# Frist_Mechanical_Arm_SCH.net
KiCad netlist of a schematic drawn in Altium Designer
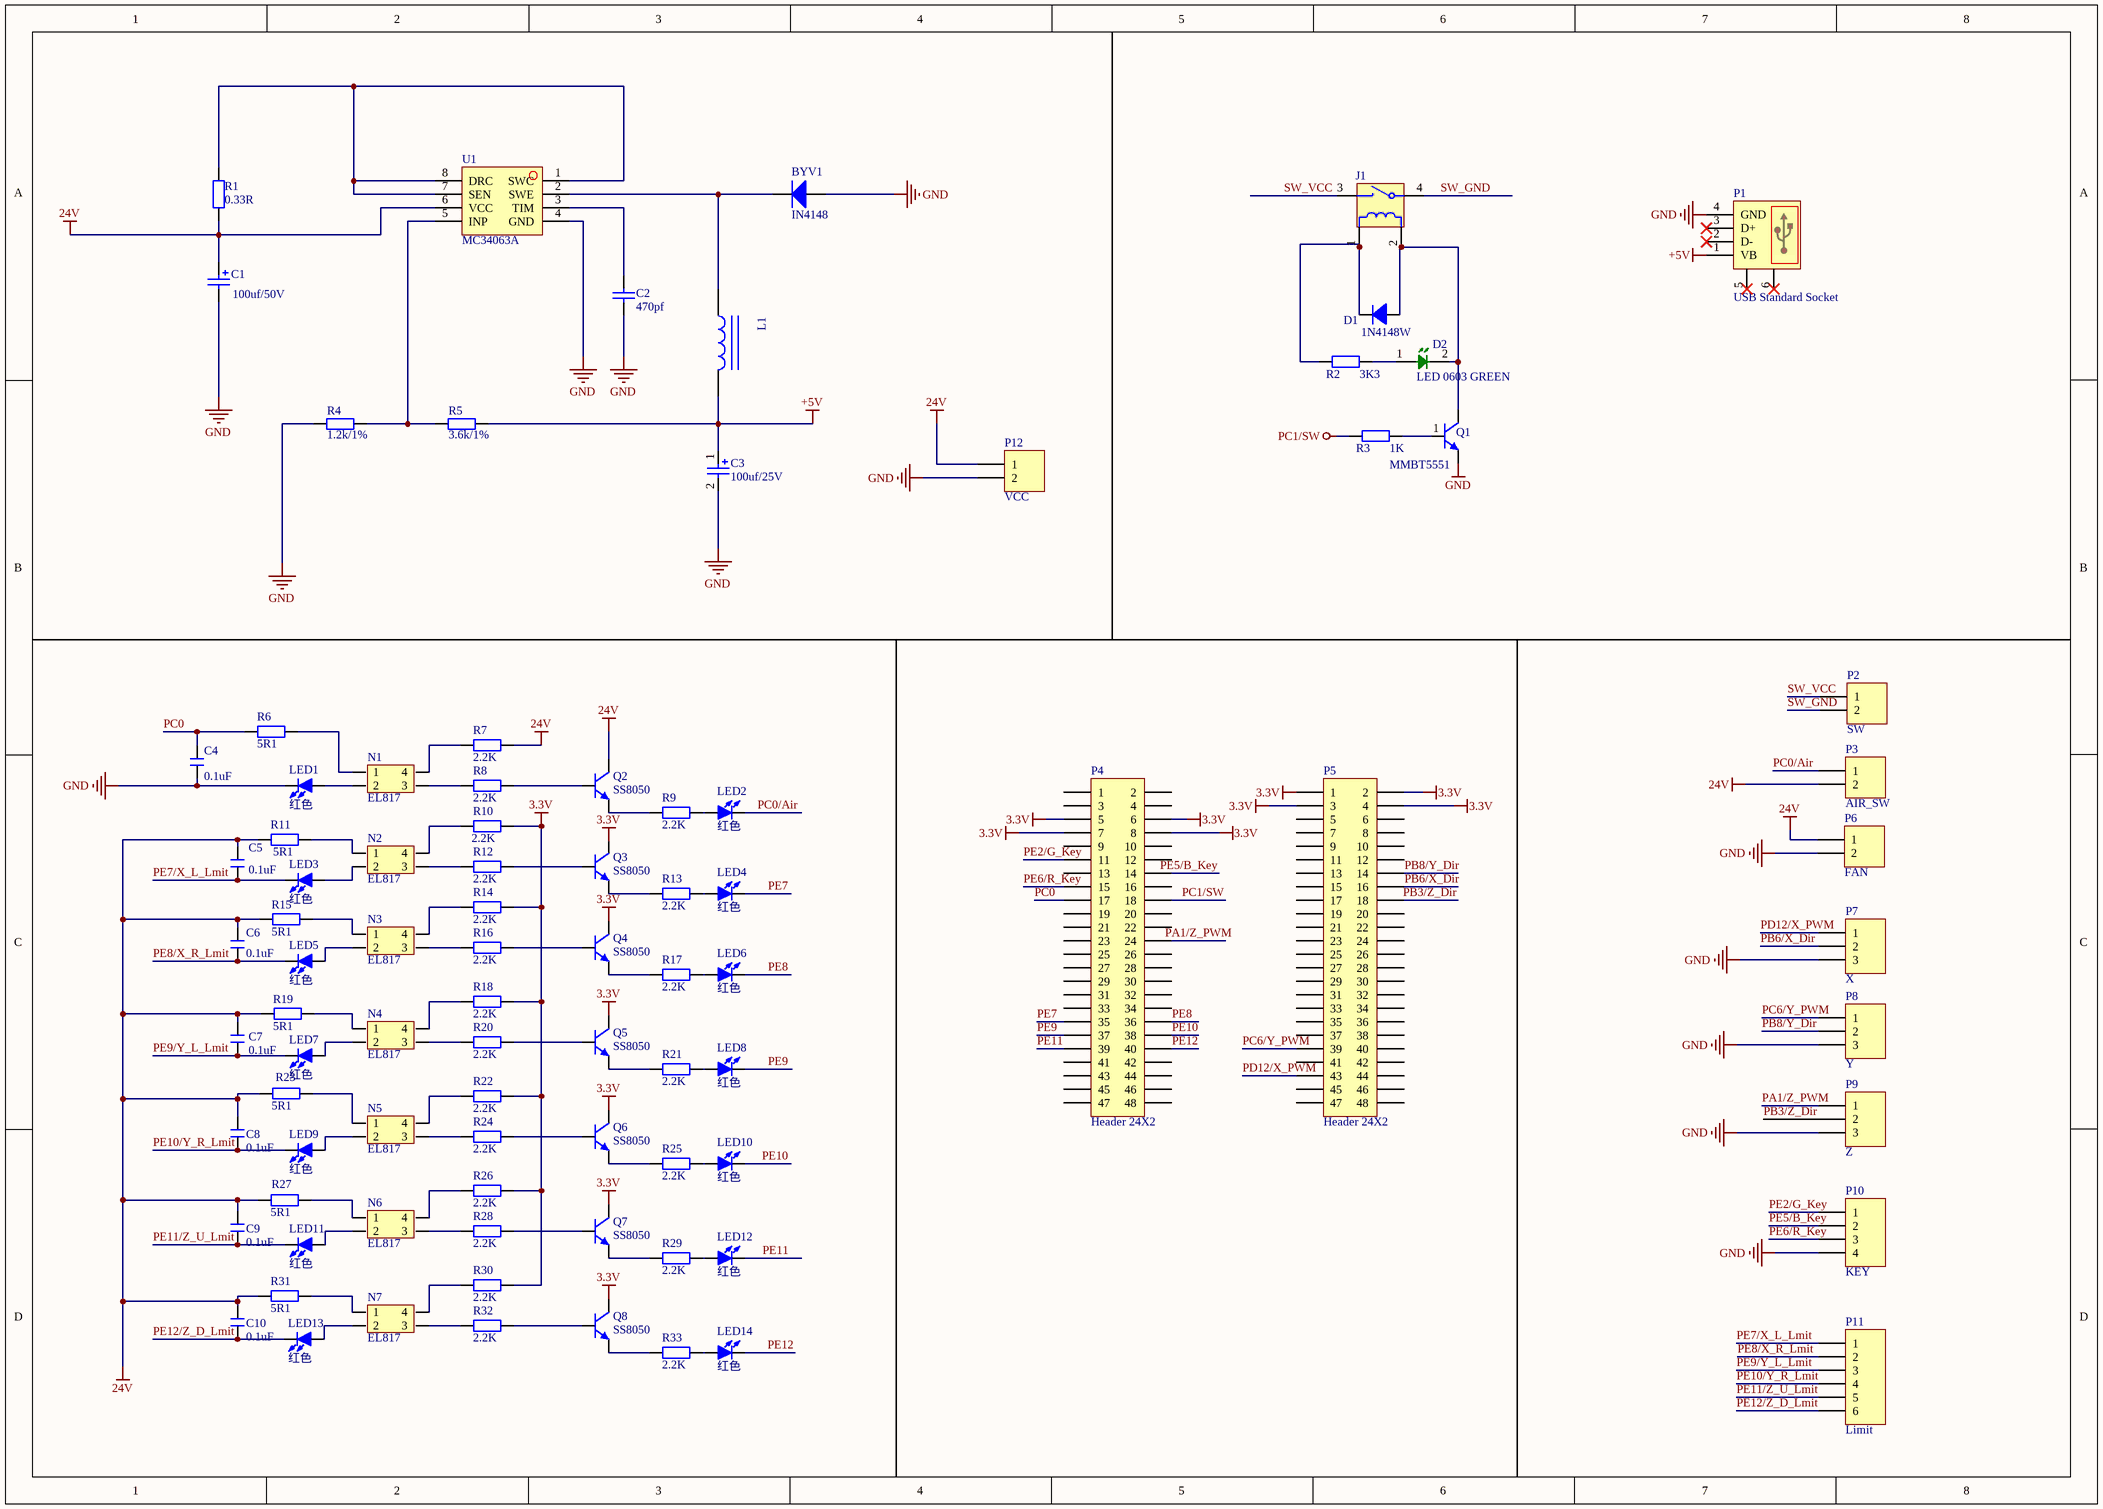
[diagram p0: Frist_Mechanical_Arm_SCH.SchDoc]

(export (version "E")
  (design (tool "Eeschema 10.0.6"))
  (components
    (comp (ref "BYV1")
      (value "BYV10-40")
      (footprint "SMA")
      (description "High Conductance Fast Diode")
      (fields (field (name "MODEL") "IN4148") (field (name "PUBLISHER") "Altium Limited"))
      (libsource (lib "全部3D") (part "Diode  Glass"))
    )
    (comp (ref "C1")
      (value "100uf")
      (footprint "CS 5.0*10*13 - R")
      (description "Polarized Capacitor (Radial)")
      (fields (field (name "VOLTAGE") "100uf/50V") (field (name "PUBLISHER") "Altium Limited"))
      (libsource (lib "全部3D") (part "Cap Pol"))
    )
    (comp (ref "C2")
      (value "470pf")
      (footprint "0603S")
      (description "Capacitor")
      (fields (field (name "PUBLISHER") "Altium Limited"))
      (libsource (lib "充放电") (part "Cap"))
    )
    (comp (ref "C3")
      (value "100uf/25V")
      (footprint "CASE7343")
      (description "Polarized Capacitor (Radial)")
      (fields
        (field (name "VOLTAGE") "16V")
        (field (name "Comment") "Cap Pol")
        (field (name "PUBLISHER") "Altium Limited")
      )
      (libsource (lib "") (part "Cap Pol_1"))
    )
    (comp (ref "C4")
      (value "0.1uF")
      (footprint "C 0805")
      (description "无极性贴片电容")
      (fields (field (name "版权归属") "源创客"))
      (libsource (lib "电阻-电容-电感") (part "C"))
    )
    (comp (ref "C5")
      (value "0.1uF")
      (footprint "C 0805")
      (description "无极性贴片电容")
      (fields (field (name "版权归属") "源创客"))
      (libsource (lib "电阻-电容-电感") (part "C"))
    )
    (comp (ref "C6")
      (value "0.1uF")
      (footprint "C 0805")
      (description "无极性贴片电容")
      (fields (field (name "版权归属") "源创客"))
      (libsource (lib "电阻-电容-电感") (part "C"))
    )
    (comp (ref "C7")
      (value "0.1uF")
      (footprint "C 0805")
      (description "无极性贴片电容")
      (fields (field (name "版权归属") "源创客"))
      (libsource (lib "电阻-电容-电感") (part "C"))
    )
    (comp (ref "C8")
      (value "0.1uF")
      (footprint "C 0805")
      (description "无极性贴片电容")
      (fields (field (name "版权归属") "源创客"))
      (libsource (lib "电阻-电容-电感") (part "C"))
    )
    (comp (ref "C9")
      (value "0.1uF")
      (footprint "C 0805")
      (description "无极性贴片电容")
      (fields (field (name "版权归属") "源创客"))
      (libsource (lib "电阻-电容-电感") (part "C"))
    )
    (comp (ref "C10")
      (value "0.1uF")
      (footprint "C 0805")
      (description "无极性贴片电容")
      (fields (field (name "版权归属") "源创客"))
      (libsource (lib "电阻-电容-电感") (part "C"))
    )
    (comp (ref "D1")
      (value "1N4148W")
      (footprint "SOD123")
      (description "HIGH-SPEED   SWITCHING DIODE")
      (libsource (lib "My Component") (part "Diode"))
    )
    (comp (ref "D2")
      (value "LED 0603 GREEN")
      (footprint "LED0805")
      (libsource (lib "My Component") (part "LED 0603 GREEN"))
    )
    (comp (ref "J1") (value "JDQ") (footprint "APAN3112") (libsource (lib "My Component") (part "PA1a")))
    (comp (ref "L1")
      (value "~")
      (footprint "L-SMD1010")
      (description "Magnetic-Core Inductor")
      (fields (field (name "PUBLISHER") "Altium Limited"))
      (libsource (lib "全部3D") (part "Inductor Iron"))
    )
    (comp (ref "LED1")
      (value "红色")
      (footprint "LED 0805G")
      (description "贴片LED")
      (fields (field (name "版权归属") "源创客"))
      (libsource (lib "LED") (part "LED-SMD"))
    )
    (comp (ref "LED2")
      (value "红色")
      (footprint "LED 0805G")
      (description "贴片LED")
      (fields (field (name "版权归属") "源创客"))
      (libsource (lib "LED") (part "LED-SMD"))
    )
    (comp (ref "LED3")
      (value "红色")
      (footprint "LED 0805G")
      (description "贴片LED")
      (fields (field (name "版权归属") "源创客"))
      (libsource (lib "LED") (part "LED-SMD"))
    )
    (comp (ref "LED4")
      (value "红色")
      (footprint "LED 0805G")
      (description "贴片LED")
      (fields (field (name "版权归属") "源创客"))
      (libsource (lib "LED") (part "LED-SMD"))
    )
    (comp (ref "LED5")
      (value "红色")
      (footprint "LED 0805G")
      (description "贴片LED")
      (fields (field (name "版权归属") "源创客"))
      (libsource (lib "LED") (part "LED-SMD"))
    )
    (comp (ref "LED6")
      (value "红色")
      (footprint "LED 0805G")
      (description "贴片LED")
      (fields (field (name "版权归属") "源创客"))
      (libsource (lib "LED") (part "LED-SMD"))
    )
    (comp (ref "LED7")
      (value "红色")
      (footprint "LED 0805G")
      (description "贴片LED")
      (fields (field (name "版权归属") "源创客"))
      (libsource (lib "LED") (part "LED-SMD"))
    )
    (comp (ref "LED8")
      (value "红色")
      (footprint "LED 0805G")
      (description "贴片LED")
      (fields (field (name "版权归属") "源创客"))
      (libsource (lib "LED") (part "LED-SMD"))
    )
    (comp (ref "LED9")
      (value "红色")
      (footprint "LED 0805G")
      (description "贴片LED")
      (fields (field (name "版权归属") "源创客"))
      (libsource (lib "LED") (part "LED-SMD"))
    )
    (comp (ref "LED10")
      (value "红色")
      (footprint "LED 0805G")
      (description "贴片LED")
      (fields (field (name "版权归属") "源创客"))
      (libsource (lib "LED") (part "LED-SMD"))
    )
    (comp (ref "LED11")
      (value "红色")
      (footprint "LED 0805G")
      (description "贴片LED")
      (fields (field (name "版权归属") "源创客"))
      (libsource (lib "LED") (part "LED-SMD"))
    )
    (comp (ref "LED12")
      (value "红色")
      (footprint "LED 0805G")
      (description "贴片LED")
      (fields (field (name "版权归属") "源创客"))
      (libsource (lib "LED") (part "LED-SMD"))
    )
    (comp (ref "LED13")
      (value "红色")
      (footprint "LED 0805G")
      (description "贴片LED")
      (fields (field (name "版权归属") "源创客"))
      (libsource (lib "LED") (part "LED-SMD"))
    )
    (comp (ref "LED14")
      (value "红色")
      (footprint "LED 0805G")
      (description "贴片LED")
      (fields (field (name "版权归属") "源创客"))
      (libsource (lib "LED") (part "LED-SMD"))
    )
    (comp (ref "N1") (value "EL817") (footprint "LC-DIP-4") (libsource (lib "我的器件") (part "EL817")))
    (comp (ref "N2") (value "EL817") (footprint "LC-DIP-4") (libsource (lib "我的器件") (part "EL817")))
    (comp (ref "N3") (value "EL817") (footprint "LC-DIP-4") (libsource (lib "我的器件") (part "EL817")))
    (comp (ref "N4") (value "EL817") (footprint "LC-DIP-4") (libsource (lib "我的器件") (part "EL817")))
    (comp (ref "N5") (value "EL817") (footprint "LC-DIP-4") (libsource (lib "我的器件") (part "EL817")))
    (comp (ref "N6") (value "EL817") (footprint "LC-DIP-4") (libsource (lib "我的器件") (part "EL817")))
    (comp (ref "N7") (value "EL817") (footprint "LC-DIP-4") (libsource (lib "我的器件") (part "EL817")))
    (comp (ref "P1")
      (value "USB Standard Socket")
      (footprint "USB Standard Socket")
      (libsource (lib "My Component") (part "USB Standard Socket"))
    )
    (comp (ref "P2")
      (value "SW")
      (footprint "KF128-3.81-2P")
      (description "Header, 2-Pin")
      (fields (field (name "PUBLISHER") "Altium Limited"))
      (libsource (lib "Miscellaneous Connectors") (part "Header 2"))
    )
    (comp (ref "P3")
      (value "AIR_SW")
      (footprint "KF128-5.08-2P")
      (description "Header, 2-Pin")
      (fields (field (name "PUBLISHER") "Altium Limited"))
      (libsource (lib "Miscellaneous Connectors") (part "Header 2"))
    )
    (comp (ref "P4")
      (value "Header 24X2")
      (footprint "HDR2X24")
      (description "Header, 24-Pin, Dual row")
      (fields (field (name "PUBLISHER") "Altium Limited"))
      (libsource (lib "Miscellaneous Connectors") (part "Header 24X2"))
    )
    (comp (ref "P5")
      (value "Header 24X2")
      (footprint "HDR2X24")
      (description "Header, 24-Pin, Dual row")
      (fields (field (name "PUBLISHER") "Altium Limited"))
      (libsource (lib "Miscellaneous Connectors") (part "Header 24X2"))
    )
    (comp (ref "P6")
      (value "FAN")
      (footprint "KF128-5.08-2P")
      (description "Header, 2-Pin")
      (fields (field (name "PUBLISHER") "Altium Limited"))
      (libsource (lib "Miscellaneous Connectors") (part "Header 2"))
    )
    (comp (ref "P7")
      (value "X")
      (footprint "KF128-5.08-3P")
      (description "Header, 3-Pin")
      (fields (field (name "PUBLISHER") "Altium Limited"))
      (libsource (lib "Miscellaneous Connectors") (part "Header 3"))
    )
    (comp (ref "P8")
      (value "Y")
      (footprint "KF128-5.08-3P")
      (description "Header, 3-Pin")
      (fields (field (name "PUBLISHER") "Altium Limited"))
      (libsource (lib "Miscellaneous Connectors") (part "Header 3"))
    )
    (comp (ref "P9")
      (value "Z")
      (footprint "KF128-5.08-3P")
      (description "Header, 3-Pin")
      (fields (field (name "PUBLISHER") "Altium Limited"))
      (libsource (lib "Miscellaneous Connectors") (part "Header 3"))
    )
    (comp (ref "P10")
      (value "KEY")
      (footprint "KF128-5.08-4P")
      (description "Header, 4-Pin")
      (fields (field (name "PUBLISHER") "Altium Limited"))
      (libsource (lib "Miscellaneous Connectors") (part "Header 4"))
    )
    (comp (ref "P11")
      (value "Limit")
      (footprint "KF128-5.08-6P")
      (description "Header, 6-Pin")
      (fields (field (name "PUBLISHER") "Altium Limited"))
      (libsource (lib "Miscellaneous Connectors") (part "Header 6"))
    )
    (comp (ref "P12")
      (value "VCC")
      (footprint "KF128-5.08-2P")
      (description "Header, 2-Pin")
      (fields (field (name "PUBLISHER") "Altium Limited"))
      (libsource (lib "Miscellaneous Connectors") (part "Header 2"))
    )
    (comp (ref "Q1")
      (value "MMBT5551")
      (footprint "SOT23-3")
      (description "SOT-23 Plastic-Encapsulate Transistors")
      (libsource (lib "My Component") (part "NPN"))
    )
    (comp (ref "Q2")
      (value "SS8050")
      (footprint "SOT23-3N")
      (description "高频放大-NPN型")
      (fields (field (name "版权归属") "源创客"))
      (libsource (lib "三极管") (part "8050-SMD"))
    )
    (comp (ref "Q3")
      (value "SS8050")
      (footprint "SOT23-3N")
      (description "高频放大-NPN型")
      (fields (field (name "版权归属") "源创客"))
      (libsource (lib "三极管") (part "8050-SMD"))
    )
    (comp (ref "Q4")
      (value "SS8050")
      (footprint "SOT23-3N")
      (description "高频放大-NPN型")
      (fields (field (name "版权归属") "源创客"))
      (libsource (lib "三极管") (part "8050-SMD"))
    )
    (comp (ref "Q5")
      (value "SS8050")
      (footprint "SOT23-3N")
      (description "高频放大-NPN型")
      (fields (field (name "版权归属") "源创客"))
      (libsource (lib "三极管") (part "8050-SMD"))
    )
    (comp (ref "Q6")
      (value "SS8050")
      (footprint "SOT23-3N")
      (description "高频放大-NPN型")
      (fields (field (name "版权归属") "源创客"))
      (libsource (lib "三极管") (part "8050-SMD"))
    )
    (comp (ref "Q7")
      (value "SS8050")
      (footprint "SOT23-3N")
      (description "高频放大-NPN型")
      (fields (field (name "版权归属") "源创客"))
      (libsource (lib "三极管") (part "8050-SMD"))
    )
    (comp (ref "Q8")
      (value "SS8050")
      (footprint "SOT23-3N")
      (description "高频放大-NPN型")
      (fields (field (name "版权归属") "源创客"))
      (libsource (lib "三极管") (part "8050-SMD"))
    )
    (comp (ref "R1")
      (value "0.33R")
      (footprint "1206R")
      (description "Resistor")
      (fields (field (name "TOLERANCE") "1%"))
      (libsource (lib "充放电") (part "Res2"))
    )
    (comp (ref "R2")
      (value "3K3")
      (footprint "0603R")
      (description "Resistor")
      (fields (field (name "TOLERANCE") "5%"))
      (libsource (lib "Miscellaneous Devices") (part "Res2"))
    )
    (comp (ref "R3")
      (value "1K")
      (footprint "0603R")
      (description "Resistor")
      (fields (field (name "TOLERANCE") "5%"))
      (libsource (lib "Miscellaneous Devices") (part "Res2"))
    )
    (comp (ref "R4")
      (value "1.2k/1%")
      (footprint "0603R")
      (description "Resistor")
      (fields (field (name "TOLERANCE") "1%"))
      (libsource (lib "") (part "Res2_1"))
    )
    (comp (ref "R5")
      (value "3.6k/1%")
      (footprint "0603R")
      (description "Resistor")
      (fields (field (name "TOLERANCE") "1%"))
      (libsource (lib "") (part "Res2_1"))
    )
    (comp (ref "R6")
      (value "5R1")
      (footprint "R 0805")
      (description "贴片电阻")
      (fields (field (name "版权归属") "源创客"))
      (libsource (lib "电阻-电容-电感") (part "R"))
    )
    (comp (ref "R7")
      (value "2.2K")
      (footprint "R 0805")
      (description "贴片电阻")
      (fields (field (name "版权归属") "源创客"))
      (libsource (lib "电阻-电容-电感") (part "R"))
    )
    (comp (ref "R8")
      (value "2.2K")
      (footprint "R 0805")
      (description "贴片电阻")
      (fields (field (name "版权归属") "源创客"))
      (libsource (lib "电阻-电容-电感") (part "R"))
    )
    (comp (ref "R9")
      (value "2.2K")
      (footprint "R 0805")
      (description "贴片电阻")
      (fields (field (name "版权归属") "源创客"))
      (libsource (lib "电阻-电容-电感") (part "R"))
    )
    (comp (ref "R10")
      (value "2.2K")
      (footprint "R 0805")
      (description "贴片电阻")
      (fields (field (name "版权归属") "源创客"))
      (libsource (lib "电阻-电容-电感") (part "R"))
    )
    (comp (ref "R11")
      (value "5R1")
      (footprint "R 0805")
      (description "贴片电阻")
      (fields (field (name "版权归属") "源创客"))
      (libsource (lib "电阻-电容-电感") (part "R"))
    )
    (comp (ref "R12")
      (value "2.2K")
      (footprint "R 0805")
      (description "贴片电阻")
      (fields (field (name "版权归属") "源创客"))
      (libsource (lib "电阻-电容-电感") (part "R"))
    )
    (comp (ref "R13")
      (value "2.2K")
      (footprint "R 0805")
      (description "贴片电阻")
      (fields (field (name "版权归属") "源创客"))
      (libsource (lib "电阻-电容-电感") (part "R"))
    )
    (comp (ref "R14")
      (value "2.2K")
      (footprint "R 0805")
      (description "贴片电阻")
      (fields (field (name "版权归属") "源创客"))
      (libsource (lib "电阻-电容-电感") (part "R"))
    )
    (comp (ref "R15")
      (value "5R1")
      (footprint "R 0805")
      (description "贴片电阻")
      (fields (field (name "版权归属") "源创客"))
      (libsource (lib "电阻-电容-电感") (part "R"))
    )
    (comp (ref "R16")
      (value "2.2K")
      (footprint "R 0805")
      (description "贴片电阻")
      (fields (field (name "版权归属") "源创客"))
      (libsource (lib "电阻-电容-电感") (part "R"))
    )
    (comp (ref "R17")
      (value "2.2K")
      (footprint "R 0805")
      (description "贴片电阻")
      (fields (field (name "版权归属") "源创客"))
      (libsource (lib "电阻-电容-电感") (part "R"))
    )
    (comp (ref "R18")
      (value "2.2K")
      (footprint "R 0805")
      (description "贴片电阻")
      (fields (field (name "版权归属") "源创客"))
      (libsource (lib "电阻-电容-电感") (part "R"))
    )
    (comp (ref "R19")
      (value "5R1")
      (footprint "R 0805")
      (description "贴片电阻")
      (fields (field (name "版权归属") "源创客"))
      (libsource (lib "电阻-电容-电感") (part "R"))
    )
    (comp (ref "R20")
      (value "2.2K")
      (footprint "R 0805")
      (description "贴片电阻")
      (fields (field (name "版权归属") "源创客"))
      (libsource (lib "电阻-电容-电感") (part "R"))
    )
    (comp (ref "R21")
      (value "2.2K")
      (footprint "R 0805")
      (description "贴片电阻")
      (fields (field (name "版权归属") "源创客"))
      (libsource (lib "电阻-电容-电感") (part "R"))
    )
    (comp (ref "R22")
      (value "2.2K")
      (footprint "R 0805")
      (description "贴片电阻")
      (fields (field (name "版权归属") "源创客"))
      (libsource (lib "电阻-电容-电感") (part "R"))
    )
    (comp (ref "R23")
      (value "5R1")
      (footprint "R 0805")
      (description "贴片电阻")
      (fields (field (name "版权归属") "源创客"))
      (libsource (lib "电阻-电容-电感") (part "R"))
    )
    (comp (ref "R24")
      (value "2.2K")
      (footprint "R 0805")
      (description "贴片电阻")
      (fields (field (name "版权归属") "源创客"))
      (libsource (lib "电阻-电容-电感") (part "R"))
    )
    (comp (ref "R25")
      (value "2.2K")
      (footprint "R 0805")
      (description "贴片电阻")
      (fields (field (name "版权归属") "源创客"))
      (libsource (lib "电阻-电容-电感") (part "R"))
    )
    (comp (ref "R26")
      (value "2.2K")
      (footprint "R 0805")
      (description "贴片电阻")
      (fields (field (name "版权归属") "源创客"))
      (libsource (lib "电阻-电容-电感") (part "R"))
    )
    (comp (ref "R27")
      (value "5R1")
      (footprint "R 0805")
      (description "贴片电阻")
      (fields (field (name "版权归属") "源创客"))
      (libsource (lib "电阻-电容-电感") (part "R"))
    )
    (comp (ref "R28")
      (value "2.2K")
      (footprint "R 0805")
      (description "贴片电阻")
      (fields (field (name "版权归属") "源创客"))
      (libsource (lib "电阻-电容-电感") (part "R"))
    )
    (comp (ref "R29")
      (value "2.2K")
      (footprint "R 0805")
      (description "贴片电阻")
      (fields (field (name "版权归属") "源创客"))
      (libsource (lib "电阻-电容-电感") (part "R"))
    )
    (comp (ref "R30")
      (value "2.2K")
      (footprint "R 0805")
      (description "贴片电阻")
      (fields (field (name "版权归属") "源创客"))
      (libsource (lib "电阻-电容-电感") (part "R"))
    )
    (comp (ref "R31")
      (value "5R1")
      (footprint "R 0805")
      (description "贴片电阻")
      (fields (field (name "版权归属") "源创客"))
      (libsource (lib "电阻-电容-电感") (part "R"))
    )
    (comp (ref "R32")
      (value "2.2K")
      (footprint "R 0805")
      (description "贴片电阻")
      (fields (field (name "版权归属") "源创客"))
      (libsource (lib "电阻-电容-电感") (part "R"))
    )
    (comp (ref "R33")
      (value "2.2K")
      (footprint "R 0805")
      (description "贴片电阻")
      (fields (field (name "版权归属") "源创客"))
      (libsource (lib "电阻-电容-电感") (part "R"))
    )
    (comp (ref "U1") (value "MC34063A") (footprint "SOP-8") (libsource (lib "SWLiB") (part "MC34063A")))
  )
  (nets
    (net (code "1") (name "+5V") (class "Default")
      (node (ref "C3") (pin "1") (pinfunction "1_1") (pintype "passive"))
      (node (ref "L1") (pin "2") (pinfunction "2_2") (pintype "passive"))
      (node (ref "P1") (pin "1") (pinfunction "VB_1") (pintype "passive"))
      (node (ref "R5") (pin "2") (pinfunction "2_2") (pintype "passive"))
    )
    (net (code "2") (name "/PA1{slash}Z_PWM") (class "Default")
      (node (ref "P4") (pin "24") (pinfunction "24_24") (pintype "passive"))
      (node (ref "P9") (pin "1") (pinfunction "1_1") (pintype "passive"))
    )
    (net (code "3") (name "/PB3{slash}Z_Dir") (class "Default")
      (node (ref "P5") (pin "18") (pinfunction "18_18") (pintype "passive"))
      (node (ref "P9") (pin "2") (pinfunction "2_2") (pintype "passive"))
    )
    (net (code "4") (name "/PB6{slash}X_Dir") (class "Default")
      (node (ref "P5") (pin "16") (pinfunction "16_16") (pintype "passive"))
      (node (ref "P7") (pin "2") (pinfunction "2_2") (pintype "passive"))
    )
    (net (code "5") (name "/PB8{slash}Y_Dir") (class "Default")
      (node (ref "P5") (pin "14") (pinfunction "14_14") (pintype "passive"))
      (node (ref "P8") (pin "2") (pinfunction "2_2") (pintype "passive"))
    )
    (net (code "6") (name "/PC0") (class "Default")
      (node (ref "C4") (pin "1") (pinfunction "1_1") (pintype "passive"))
      (node (ref "P4") (pin "17") (pinfunction "17_17") (pintype "passive"))
      (node (ref "R6") (pin "1") (pinfunction "1_1") (pintype "passive"))
    )
    (net (code "7") (name "/PC0{slash}Air") (class "Default")
      (node (ref "LED2") (pin "2") (pinfunction "K_2") (pintype "passive"))
      (node (ref "P3") (pin "1") (pinfunction "1_1") (pintype "passive"))
    )
    (net (code "8") (name "/PC6{slash}Y_PWM") (class "Default")
      (node (ref "P5") (pin "39") (pinfunction "39_39") (pintype "passive"))
      (node (ref "P8") (pin "1") (pinfunction "1_1") (pintype "passive"))
    )
    (net (code "9") (name "/PD12{slash}X_PWM") (class "Default")
      (node (ref "P5") (pin "43") (pinfunction "43_43") (pintype "passive"))
      (node (ref "P7") (pin "1") (pinfunction "1_1") (pintype "passive"))
    )
    (net (code "10") (name "/PE2{slash}G_Key") (class "Default")
      (node (ref "P10") (pin "1") (pinfunction "1_1") (pintype "passive"))
      (node (ref "P4") (pin "11") (pinfunction "11_11") (pintype "passive"))
    )
    (net (code "11") (name "/PE5{slash}B_Key") (class "Default")
      (node (ref "P10") (pin "2") (pinfunction "2_2") (pintype "passive"))
      (node (ref "P4") (pin "14") (pinfunction "14_14") (pintype "passive"))
    )
    (net (code "12") (name "/PE6{slash}R_Key") (class "Default")
      (node (ref "P10") (pin "3") (pinfunction "3_3") (pintype "passive"))
      (node (ref "P4") (pin "15") (pinfunction "15_15") (pintype "passive"))
    )
    (net (code "13") (name "/PE7") (class "Default")
      (node (ref "LED4") (pin "2") (pinfunction "K_2") (pintype "passive"))
      (node (ref "P4") (pin "35") (pinfunction "35_35") (pintype "passive"))
    )
    (net (code "14") (name "/PE7{slash}X_L_Lmit") (class "Default")
      (node (ref "C5") (pin "1") (pinfunction "1_1") (pintype "passive"))
      (node (ref "LED3") (pin "2") (pinfunction "K_2") (pintype "passive"))
      (node (ref "P11") (pin "1") (pinfunction "1_1") (pintype "passive"))
    )
    (net (code "15") (name "/PE8") (class "Default")
      (node (ref "LED6") (pin "2") (pinfunction "K_2") (pintype "passive"))
      (node (ref "P4") (pin "36") (pinfunction "36_36") (pintype "passive"))
    )
    (net (code "16") (name "/PE8{slash}X_R_Lmit") (class "Default")
      (node (ref "C6") (pin "1") (pinfunction "1_1") (pintype "passive"))
      (node (ref "LED5") (pin "2") (pinfunction "K_2") (pintype "passive"))
      (node (ref "P11") (pin "2") (pinfunction "2_2") (pintype "passive"))
    )
    (net (code "17") (name "/PE9") (class "Default")
      (node (ref "LED8") (pin "2") (pinfunction "K_2") (pintype "passive"))
      (node (ref "P4") (pin "37") (pinfunction "37_37") (pintype "passive"))
    )
    (net (code "18") (name "/PE9{slash}Y_L_Lmit") (class "Default")
      (node (ref "C7") (pin "1") (pinfunction "1_1") (pintype "passive"))
      (node (ref "LED7") (pin "2") (pinfunction "K_2") (pintype "passive"))
      (node (ref "P11") (pin "3") (pinfunction "3_3") (pintype "passive"))
    )
    (net (code "19") (name "/PE10") (class "Default")
      (node (ref "LED10") (pin "2") (pinfunction "K_2") (pintype "passive"))
      (node (ref "P4") (pin "38") (pinfunction "38_38") (pintype "passive"))
    )
    (net (code "20") (name "/PE10{slash}Y_R_Lmit") (class "Default")
      (node (ref "C8") (pin "1") (pinfunction "1_1") (pintype "passive"))
      (node (ref "LED9") (pin "2") (pinfunction "K_2") (pintype "passive"))
      (node (ref "P11") (pin "4") (pinfunction "4_4") (pintype "passive"))
    )
    (net (code "21") (name "/PE11") (class "Default")
      (node (ref "LED12") (pin "2") (pinfunction "K_2") (pintype "passive"))
      (node (ref "P4") (pin "39") (pinfunction "39_39") (pintype "passive"))
    )
    (net (code "22") (name "/PE11{slash}Z_U_Lmit") (class "Default")
      (node (ref "C9") (pin "1") (pinfunction "1_1") (pintype "passive"))
      (node (ref "LED11") (pin "2") (pinfunction "K_2") (pintype "passive"))
      (node (ref "P11") (pin "5") (pinfunction "5_5") (pintype "passive"))
    )
    (net (code "23") (name "/PE12") (class "Default")
      (node (ref "LED14") (pin "2") (pinfunction "K_2") (pintype "passive"))
      (node (ref "P4") (pin "40") (pinfunction "40_40") (pintype "passive"))
    )
    (net (code "24") (name "/PE12{slash}Z_D_Lmit") (class "Default")
      (node (ref "C10") (pin "1") (pinfunction "1_1") (pintype "passive"))
      (node (ref "LED13") (pin "2") (pinfunction "K_2") (pintype "passive"))
      (node (ref "P11") (pin "6") (pinfunction "6_6") (pintype "passive"))
    )
    (net (code "25") (name "/SW_GND") (class "Default")
      (node (ref "J1") (pin "4") (pinfunction "4_4") (pintype "passive"))
      (node (ref "P2") (pin "2") (pinfunction "2_2") (pintype "passive"))
    )
    (net (code "26") (name "/SW_VCC") (class "Default")
      (node (ref "J1") (pin "3") (pinfunction "3_3") (pintype "passive"))
      (node (ref "P2") (pin "1") (pinfunction "1_1") (pintype "passive"))
    )
    (net (code "27") (name "3.3V") (class "Default")
      (node (ref "P4") (pin "5") (pinfunction "5_5") (pintype "passive"))
      (node (ref "P4") (pin "6") (pinfunction "6_6") (pintype "passive"))
      (node (ref "P4") (pin "7") (pinfunction "7_7") (pintype "passive"))
      (node (ref "P4") (pin "8") (pinfunction "8_8") (pintype "passive"))
      (node (ref "P5") (pin "1") (pinfunction "1_1") (pintype "passive"))
      (node (ref "P5") (pin "2") (pinfunction "2_2") (pintype "passive"))
      (node (ref "P5") (pin "3") (pinfunction "3_3") (pintype "passive"))
      (node (ref "P5") (pin "4") (pinfunction "4_4") (pintype "passive"))
      (node (ref "Q4") (pin "3") (pinfunction "C_3") (pintype "passive"))
      (node (ref "Q5") (pin "3") (pinfunction "C_3") (pintype "passive"))
      (node (ref "Q6") (pin "3") (pinfunction "C_3") (pintype "passive"))
      (node (ref "Q7") (pin "3") (pinfunction "C_3") (pintype "passive"))
      (node (ref "Q8") (pin "3") (pinfunction "C_3") (pintype "passive"))
      (node (ref "R10") (pin "2") (pinfunction "2_2") (pintype "passive"))
      (node (ref "R14") (pin "2") (pinfunction "2_2") (pintype "passive"))
      (node (ref "R18") (pin "2") (pinfunction "2_2") (pintype "passive"))
      (node (ref "R22") (pin "2") (pinfunction "2_2") (pintype "passive"))
      (node (ref "R26") (pin "2") (pinfunction "2_2") (pintype "passive"))
      (node (ref "R30") (pin "2") (pinfunction "2_2") (pintype "passive"))
    )
    (net (code "28") (name "24V") (class "Default")
      (node (ref "C1") (pin "1") (pinfunction "1_1") (pintype "passive"))
      (node (ref "C10") (pin "2") (pinfunction "2_2") (pintype "passive"))
      (node (ref "C5") (pin "2") (pinfunction "2_2") (pintype "passive"))
      (node (ref "C6") (pin "2") (pinfunction "2_2") (pintype "passive"))
      (node (ref "C7") (pin "2") (pinfunction "2_2") (pintype "passive"))
      (node (ref "C8") (pin "2") (pinfunction "2_2") (pintype "passive"))
      (node (ref "C9") (pin "2") (pinfunction "2_2") (pintype "passive"))
      (node (ref "P12") (pin "1") (pinfunction "1_1") (pintype "passive"))
      (node (ref "P3") (pin "2") (pinfunction "2_2") (pintype "passive"))
      (node (ref "P6") (pin "1") (pinfunction "1_1") (pintype "passive"))
      (node (ref "Q2") (pin "3") (pinfunction "C_3") (pintype "passive"))
      (node (ref "R1") (pin "1") (pinfunction "1_1") (pintype "passive"))
      (node (ref "R11") (pin "1") (pinfunction "1_1") (pintype "passive"))
      (node (ref "R15") (pin "1") (pinfunction "1_1") (pintype "passive"))
      (node (ref "R19") (pin "1") (pinfunction "1_1") (pintype "passive"))
      (node (ref "R23") (pin "1") (pinfunction "1_1") (pintype "passive"))
      (node (ref "R27") (pin "1") (pinfunction "1_1") (pintype "passive"))
      (node (ref "R31") (pin "1") (pinfunction "1_1") (pintype "passive"))
      (node (ref "R7") (pin "2") (pinfunction "2_2") (pintype "passive"))
      (node (ref "U1") (pin "6") (pinfunction "VCC_6") (pintype "passive"))
    )
    (net (code "29") (name "GND") (class "Default")
      (node (ref "BYV1") (pin "1") (pinfunction "A_1") (pintype "passive"))
      (node (ref "C1") (pin "2") (pinfunction "2_2") (pintype "passive"))
      (node (ref "C2") (pin "1") (pinfunction "1_1") (pintype "passive"))
      (node (ref "C3") (pin "2") (pinfunction "2_2") (pintype "passive"))
      (node (ref "C4") (pin "2") (pinfunction "2_2") (pintype "passive"))
      (node (ref "LED1") (pin "2") (pinfunction "K_2") (pintype "passive"))
      (node (ref "P1") (pin "4") (pinfunction "GND_4") (pintype "passive"))
      (node (ref "P10") (pin "4") (pinfunction "4_4") (pintype "passive"))
      (node (ref "P12") (pin "2") (pinfunction "2_2") (pintype "passive"))
      (node (ref "P6") (pin "2") (pinfunction "2_2") (pintype "passive"))
      (node (ref "P7") (pin "3") (pinfunction "3_3") (pintype "passive"))
      (node (ref "P8") (pin "3") (pinfunction "3_3") (pintype "passive"))
      (node (ref "P9") (pin "3") (pinfunction "3_3") (pintype "passive"))
      (node (ref "Q1") (pin "2") (pintype "passive"))
      (node (ref "R4") (pin "1") (pinfunction "1_1") (pintype "passive"))
      (node (ref "U1") (pin "4") (pinfunction "GND_4") (pintype "passive"))
    )
    (net (code "30") (name "Net-(BYV1-K)") (class "Default")
      (node (ref "BYV1") (pin "2") (pinfunction "K_2") (pintype "passive"))
      (node (ref "L1") (pin "1") (pinfunction "1_1") (pintype "passive"))
      (node (ref "U1") (pin "2") (pinfunction "SWE_2") (pintype "passive"))
    )
    (net (code "31") (name "Net-(D1-A)") (class "Default")
      (node (ref "D1") (pin "1") (pinfunction "A_1") (pintype "passive"))
      (node (ref "D2") (pin "2") (pinfunction "2_2") (pintype "passive"))
      (node (ref "J1") (pin "2") (pinfunction "2_2") (pintype "passive"))
      (node (ref "Q1") (pin "3") (pintype "passive"))
    )
    (net (code "32") (name "Net-(D1-K)") (class "Default")
      (node (ref "D1") (pin "2") (pinfunction "K_2") (pintype "passive"))
      (node (ref "J1") (pin "1") (pinfunction "1_1") (pintype "passive"))
      (node (ref "R2") (pin "1") (pinfunction "1_1") (pintype "passive"))
    )
    (net (code "33") (name "Net-(D2-Pad1)") (class "Default")
      (node (ref "D2") (pin "1") (pinfunction "1_1") (pintype "passive"))
      (node (ref "R2") (pin "2") (pinfunction "2_2") (pintype "passive"))
    )
    (net (code "34") (name "Net-(LED1-A)") (class "Default")
      (node (ref "LED1") (pin "1") (pinfunction "A_1") (pintype "passive"))
      (node (ref "N1") (pin "2") (pinfunction "2_2") (pintype "passive"))
    )
    (net (code "35") (name "Net-(LED2-A)") (class "Default")
      (node (ref "LED2") (pin "1") (pinfunction "A_1") (pintype "passive"))
      (node (ref "R9") (pin "2") (pinfunction "2_2") (pintype "passive"))
    )
    (net (code "36") (name "Net-(LED3-A)") (class "Default")
      (node (ref "LED3") (pin "1") (pinfunction "A_1") (pintype "passive"))
      (node (ref "N2") (pin "2") (pinfunction "2_2") (pintype "passive"))
    )
    (net (code "37") (name "Net-(LED4-A)") (class "Default")
      (node (ref "LED4") (pin "1") (pinfunction "A_1") (pintype "passive"))
      (node (ref "R13") (pin "2") (pinfunction "2_2") (pintype "passive"))
    )
    (net (code "38") (name "Net-(LED5-A)") (class "Default")
      (node (ref "LED5") (pin "1") (pinfunction "A_1") (pintype "passive"))
      (node (ref "N3") (pin "2") (pinfunction "2_2") (pintype "passive"))
    )
    (net (code "39") (name "Net-(LED6-A)") (class "Default")
      (node (ref "LED6") (pin "1") (pinfunction "A_1") (pintype "passive"))
      (node (ref "R17") (pin "2") (pinfunction "2_2") (pintype "passive"))
    )
    (net (code "40") (name "Net-(LED7-A)") (class "Default")
      (node (ref "LED7") (pin "1") (pinfunction "A_1") (pintype "passive"))
      (node (ref "N4") (pin "2") (pinfunction "2_2") (pintype "passive"))
    )
    (net (code "41") (name "Net-(LED8-A)") (class "Default")
      (node (ref "LED8") (pin "1") (pinfunction "A_1") (pintype "passive"))
      (node (ref "R21") (pin "2") (pinfunction "2_2") (pintype "passive"))
    )
    (net (code "42") (name "Net-(LED9-A)") (class "Default")
      (node (ref "LED9") (pin "1") (pinfunction "A_1") (pintype "passive"))
      (node (ref "N5") (pin "2") (pinfunction "2_2") (pintype "passive"))
    )
    (net (code "43") (name "Net-(LED10-A)") (class "Default")
      (node (ref "LED10") (pin "1") (pinfunction "A_1") (pintype "passive"))
      (node (ref "R25") (pin "2") (pinfunction "2_2") (pintype "passive"))
    )
    (net (code "44") (name "Net-(LED11-A)") (class "Default")
      (node (ref "LED11") (pin "1") (pinfunction "A_1") (pintype "passive"))
      (node (ref "N6") (pin "2") (pinfunction "2_2") (pintype "passive"))
    )
    (net (code "45") (name "Net-(LED12-A)") (class "Default")
      (node (ref "LED12") (pin "1") (pinfunction "A_1") (pintype "passive"))
      (node (ref "R29") (pin "2") (pinfunction "2_2") (pintype "passive"))
    )
    (net (code "46") (name "Net-(LED13-A)") (class "Default")
      (node (ref "LED13") (pin "1") (pinfunction "A_1") (pintype "passive"))
      (node (ref "N7") (pin "2") (pinfunction "2_2") (pintype "passive"))
    )
    (net (code "47") (name "Net-(LED14-A)") (class "Default")
      (node (ref "LED14") (pin "1") (pinfunction "A_1") (pintype "passive"))
      (node (ref "R33") (pin "2") (pinfunction "2_2") (pintype "passive"))
    )
    (net (code "48") (name "Net-(N1-Pad1)") (class "Default")
      (node (ref "N1") (pin "1") (pinfunction "1_1") (pintype "passive"))
      (node (ref "R6") (pin "2") (pinfunction "2_2") (pintype "passive"))
    )
    (net (code "49") (name "Net-(N1-Pad3)") (class "Default")
      (node (ref "N1") (pin "3") (pinfunction "3_3") (pintype "passive"))
      (node (ref "R8") (pin "1") (pinfunction "1_1") (pintype "passive"))
    )
    (net (code "50") (name "Net-(N1-Pad4)") (class "Default")
      (node (ref "N1") (pin "4") (pinfunction "4_4") (pintype "passive"))
      (node (ref "R7") (pin "1") (pinfunction "1_1") (pintype "passive"))
    )
    (net (code "51") (name "Net-(N2-Pad1)") (class "Default")
      (node (ref "N2") (pin "1") (pinfunction "1_1") (pintype "passive"))
      (node (ref "R11") (pin "2") (pinfunction "2_2") (pintype "passive"))
    )
    (net (code "52") (name "Net-(N2-Pad3)") (class "Default")
      (node (ref "N2") (pin "3") (pinfunction "3_3") (pintype "passive"))
      (node (ref "R12") (pin "1") (pinfunction "1_1") (pintype "passive"))
    )
    (net (code "53") (name "Net-(N2-Pad4)") (class "Default")
      (node (ref "N2") (pin "4") (pinfunction "4_4") (pintype "passive"))
      (node (ref "R10") (pin "1") (pinfunction "1_1") (pintype "passive"))
    )
    (net (code "54") (name "Net-(N3-Pad1)") (class "Default")
      (node (ref "N3") (pin "1") (pinfunction "1_1") (pintype "passive"))
      (node (ref "R15") (pin "2") (pinfunction "2_2") (pintype "passive"))
    )
    (net (code "55") (name "Net-(N3-Pad3)") (class "Default")
      (node (ref "N3") (pin "3") (pinfunction "3_3") (pintype "passive"))
      (node (ref "R16") (pin "1") (pinfunction "1_1") (pintype "passive"))
    )
    (net (code "56") (name "Net-(N3-Pad4)") (class "Default")
      (node (ref "N3") (pin "4") (pinfunction "4_4") (pintype "passive"))
      (node (ref "R14") (pin "1") (pinfunction "1_1") (pintype "passive"))
    )
    (net (code "57") (name "Net-(N4-Pad1)") (class "Default")
      (node (ref "N4") (pin "1") (pinfunction "1_1") (pintype "passive"))
      (node (ref "R19") (pin "2") (pinfunction "2_2") (pintype "passive"))
    )
    (net (code "58") (name "Net-(N4-Pad3)") (class "Default")
      (node (ref "N4") (pin "3") (pinfunction "3_3") (pintype "passive"))
      (node (ref "R20") (pin "1") (pinfunction "1_1") (pintype "passive"))
    )
    (net (code "59") (name "Net-(N4-Pad4)") (class "Default")
      (node (ref "N4") (pin "4") (pinfunction "4_4") (pintype "passive"))
      (node (ref "R18") (pin "1") (pinfunction "1_1") (pintype "passive"))
    )
    (net (code "60") (name "Net-(N5-Pad1)") (class "Default")
      (node (ref "N5") (pin "1") (pinfunction "1_1") (pintype "passive"))
      (node (ref "R23") (pin "2") (pinfunction "2_2") (pintype "passive"))
    )
    (net (code "61") (name "Net-(N5-Pad3)") (class "Default")
      (node (ref "N5") (pin "3") (pinfunction "3_3") (pintype "passive"))
      (node (ref "R24") (pin "1") (pinfunction "1_1") (pintype "passive"))
    )
    (net (code "62") (name "Net-(N5-Pad4)") (class "Default")
      (node (ref "N5") (pin "4") (pinfunction "4_4") (pintype "passive"))
      (node (ref "R22") (pin "1") (pinfunction "1_1") (pintype "passive"))
    )
    (net (code "63") (name "Net-(N6-Pad1)") (class "Default")
      (node (ref "N6") (pin "1") (pinfunction "1_1") (pintype "passive"))
      (node (ref "R27") (pin "2") (pinfunction "2_2") (pintype "passive"))
    )
    (net (code "64") (name "Net-(N6-Pad3)") (class "Default")
      (node (ref "N6") (pin "3") (pinfunction "3_3") (pintype "passive"))
      (node (ref "R28") (pin "1") (pinfunction "1_1") (pintype "passive"))
    )
    (net (code "65") (name "Net-(N6-Pad4)") (class "Default")
      (node (ref "N6") (pin "4") (pinfunction "4_4") (pintype "passive"))
      (node (ref "R26") (pin "1") (pinfunction "1_1") (pintype "passive"))
    )
    (net (code "66") (name "Net-(N7-Pad1)") (class "Default")
      (node (ref "N7") (pin "1") (pinfunction "1_1") (pintype "passive"))
      (node (ref "R31") (pin "2") (pinfunction "2_2") (pintype "passive"))
    )
    (net (code "67") (name "Net-(N7-Pad3)") (class "Default")
      (node (ref "N7") (pin "3") (pinfunction "3_3") (pintype "passive"))
      (node (ref "R32") (pin "1") (pinfunction "1_1") (pintype "passive"))
    )
    (net (code "68") (name "Net-(N7-Pad4)") (class "Default")
      (node (ref "N7") (pin "4") (pinfunction "4_4") (pintype "passive"))
      (node (ref "R30") (pin "1") (pinfunction "1_1") (pintype "passive"))
    )
    (net (code "69") (name "Net-(Q1-Pad1)") (class "Default")
      (node (ref "Q1") (pin "1") (pintype "passive"))
      (node (ref "R3") (pin "2") (pinfunction "2_2") (pintype "passive"))
    )
    (net (code "70") (name "Net-(Q2-B)") (class "Default")
      (node (ref "Q2") (pin "1") (pinfunction "B_1") (pintype "passive"))
      (node (ref "R8") (pin "2") (pinfunction "2_2") (pintype "passive"))
    )
    (net (code "71") (name "Net-(Q2-E)") (class "Default")
      (node (ref "Q2") (pin "2") (pinfunction "E_2") (pintype "passive"))
      (node (ref "R9") (pin "1") (pinfunction "1_1") (pintype "passive"))
    )
    (net (code "72") (name "Net-(Q3-B)") (class "Default")
      (node (ref "Q3") (pin "1") (pinfunction "B_1") (pintype "passive"))
      (node (ref "R12") (pin "2") (pinfunction "2_2") (pintype "passive"))
    )
    (net (code "73") (name "Net-(Q3-E)") (class "Default")
      (node (ref "Q3") (pin "2") (pinfunction "E_2") (pintype "passive"))
      (node (ref "R13") (pin "1") (pinfunction "1_1") (pintype "passive"))
    )
    (net (code "74") (name "Net-(Q4-B)") (class "Default")
      (node (ref "Q4") (pin "1") (pinfunction "B_1") (pintype "passive"))
      (node (ref "R16") (pin "2") (pinfunction "2_2") (pintype "passive"))
    )
    (net (code "75") (name "Net-(Q4-E)") (class "Default")
      (node (ref "Q4") (pin "2") (pinfunction "E_2") (pintype "passive"))
      (node (ref "R17") (pin "1") (pinfunction "1_1") (pintype "passive"))
    )
    (net (code "76") (name "Net-(Q5-B)") (class "Default")
      (node (ref "Q5") (pin "1") (pinfunction "B_1") (pintype "passive"))
      (node (ref "R20") (pin "2") (pinfunction "2_2") (pintype "passive"))
    )
    (net (code "77") (name "Net-(Q5-E)") (class "Default")
      (node (ref "Q5") (pin "2") (pinfunction "E_2") (pintype "passive"))
      (node (ref "R21") (pin "1") (pinfunction "1_1") (pintype "passive"))
    )
    (net (code "78") (name "Net-(Q6-B)") (class "Default")
      (node (ref "Q6") (pin "1") (pinfunction "B_1") (pintype "passive"))
      (node (ref "R24") (pin "2") (pinfunction "2_2") (pintype "passive"))
    )
    (net (code "79") (name "Net-(Q6-E)") (class "Default")
      (node (ref "Q6") (pin "2") (pinfunction "E_2") (pintype "passive"))
      (node (ref "R25") (pin "1") (pinfunction "1_1") (pintype "passive"))
    )
    (net (code "80") (name "Net-(Q7-B)") (class "Default")
      (node (ref "Q7") (pin "1") (pinfunction "B_1") (pintype "passive"))
      (node (ref "R28") (pin "2") (pinfunction "2_2") (pintype "passive"))
    )
    (net (code "81") (name "Net-(Q7-E)") (class "Default")
      (node (ref "Q7") (pin "2") (pinfunction "E_2") (pintype "passive"))
      (node (ref "R29") (pin "1") (pinfunction "1_1") (pintype "passive"))
    )
    (net (code "82") (name "Net-(Q8-B)") (class "Default")
      (node (ref "Q8") (pin "1") (pinfunction "B_1") (pintype "passive"))
      (node (ref "R32") (pin "2") (pinfunction "2_2") (pintype "passive"))
    )
    (net (code "83") (name "Net-(Q8-E)") (class "Default")
      (node (ref "Q8") (pin "2") (pinfunction "E_2") (pintype "passive"))
      (node (ref "R33") (pin "1") (pinfunction "1_1") (pintype "passive"))
    )
    (net (code "84") (name "Net-(U1-DRC)") (class "Default")
      (node (ref "R1") (pin "2") (pinfunction "2_2") (pintype "passive"))
      (node (ref "U1") (pin "1") (pinfunction "SWC_1") (pintype "passive"))
      (node (ref "U1") (pin "7") (pinfunction "SEN_7") (pintype "passive"))
      (node (ref "U1") (pin "8") (pinfunction "DRC_8") (pintype "passive"))
    )
    (net (code "85") (name "Net-(U1-INP)") (class "Default")
      (node (ref "R4") (pin "2") (pinfunction "2_2") (pintype "passive"))
      (node (ref "R5") (pin "1") (pinfunction "1_1") (pintype "passive"))
      (node (ref "U1") (pin "5") (pinfunction "INP_5") (pintype "passive"))
    )
    (net (code "86") (name "Net-(U1-TIM)") (class "Default")
      (node (ref "C2") (pin "2") (pinfunction "2_2") (pintype "passive"))
      (node (ref "U1") (pin "3") (pinfunction "TIM_3") (pintype "passive"))
    )
    (net (code "87") (name "PC1{slash}SW") (class "Default")
      (node (ref "P4") (pin "18") (pinfunction "18_18") (pintype "passive"))
      (node (ref "R3") (pin "1") (pinfunction "1_1") (pintype "passive"))
    )
    (net (code "88") (name "unconnected-(P1-D+-Pad3)") (class "Default")
      (node (ref "P1") (pin "3") (pinfunction "D+_3") (pintype "passive+no_connect"))
    )
    (net (code "89") (name "unconnected-(P1-D--Pad2)") (class "Default")
      (node (ref "P1") (pin "2") (pinfunction "D-_2") (pintype "passive+no_connect"))
    )
    (net (code "90") (name "unconnected-(P1-Pad5)") (class "Default")
      (node (ref "P1") (pin "5") (pinfunction "5_5") (pintype "passive+no_connect"))
    )
    (net (code "91") (name "unconnected-(P1-Pad6)") (class "Default")
      (node (ref "P1") (pin "6") (pinfunction "6_6") (pintype "passive+no_connect"))
    )
    (net (code "92") (name "unconnected-(P4-Pad1)") (class "Default")
      (node (ref "P4") (pin "1") (pinfunction "1_1") (pintype "passive"))
    )
    (net (code "93") (name "unconnected-(P4-Pad2)") (class "Default")
      (node (ref "P4") (pin "2") (pinfunction "2_2") (pintype "passive"))
    )
    (net (code "94") (name "unconnected-(P4-Pad3)") (class "Default")
      (node (ref "P4") (pin "3") (pinfunction "3_3") (pintype "passive"))
    )
    (net (code "95") (name "unconnected-(P4-Pad4)") (class "Default")
      (node (ref "P4") (pin "4") (pinfunction "4_4") (pintype "passive"))
    )
    (net (code "96") (name "unconnected-(P4-Pad9)") (class "Default")
      (node (ref "P4") (pin "9") (pinfunction "9_9") (pintype "passive"))
    )
    (net (code "97") (name "unconnected-(P4-Pad10)") (class "Default")
      (node (ref "P4") (pin "10") (pinfunction "10_10") (pintype "passive"))
    )
    (net (code "98") (name "unconnected-(P4-Pad12)") (class "Default")
      (node (ref "P4") (pin "12") (pinfunction "12_12") (pintype "passive"))
    )
    (net (code "99") (name "unconnected-(P4-Pad13)") (class "Default")
      (node (ref "P4") (pin "13") (pinfunction "13_13") (pintype "passive"))
    )
    (net (code "100") (name "unconnected-(P4-Pad16)") (class "Default")
      (node (ref "P4") (pin "16") (pinfunction "16_16") (pintype "passive"))
    )
    (net (code "101") (name "unconnected-(P4-Pad19)") (class "Default")
      (node (ref "P4") (pin "19") (pinfunction "19_19") (pintype "passive"))
    )
    (net (code "102") (name "unconnected-(P4-Pad20)") (class "Default")
      (node (ref "P4") (pin "20") (pinfunction "20_20") (pintype "passive"))
    )
    (net (code "103") (name "unconnected-(P4-Pad21)") (class "Default")
      (node (ref "P4") (pin "21") (pinfunction "21_21") (pintype "passive"))
    )
    (net (code "104") (name "unconnected-(P4-Pad22)") (class "Default")
      (node (ref "P4") (pin "22") (pinfunction "22_22") (pintype "passive"))
    )
    (net (code "105") (name "unconnected-(P4-Pad23)") (class "Default")
      (node (ref "P4") (pin "23") (pinfunction "23_23") (pintype "passive"))
    )
    (net (code "106") (name "unconnected-(P4-Pad25)") (class "Default")
      (node (ref "P4") (pin "25") (pinfunction "25_25") (pintype "passive"))
    )
    (net (code "107") (name "unconnected-(P4-Pad26)") (class "Default")
      (node (ref "P4") (pin "26") (pinfunction "26_26") (pintype "passive"))
    )
    (net (code "108") (name "unconnected-(P4-Pad27)") (class "Default")
      (node (ref "P4") (pin "27") (pinfunction "27_27") (pintype "passive"))
    )
    (net (code "109") (name "unconnected-(P4-Pad28)") (class "Default")
      (node (ref "P4") (pin "28") (pinfunction "28_28") (pintype "passive"))
    )
    (net (code "110") (name "unconnected-(P4-Pad29)") (class "Default")
      (node (ref "P4") (pin "29") (pinfunction "29_29") (pintype "passive"))
    )
    (net (code "111") (name "unconnected-(P4-Pad30)") (class "Default")
      (node (ref "P4") (pin "30") (pinfunction "30_30") (pintype "passive"))
    )
    (net (code "112") (name "unconnected-(P4-Pad31)") (class "Default")
      (node (ref "P4") (pin "31") (pinfunction "31_31") (pintype "passive"))
    )
    (net (code "113") (name "unconnected-(P4-Pad32)") (class "Default")
      (node (ref "P4") (pin "32") (pinfunction "32_32") (pintype "passive"))
    )
    (net (code "114") (name "unconnected-(P4-Pad33)") (class "Default")
      (node (ref "P4") (pin "33") (pinfunction "33_33") (pintype "passive"))
    )
    (net (code "115") (name "unconnected-(P4-Pad34)") (class "Default")
      (node (ref "P4") (pin "34") (pinfunction "34_34") (pintype "passive"))
    )
    (net (code "116") (name "unconnected-(P4-Pad41)") (class "Default")
      (node (ref "P4") (pin "41") (pinfunction "41_41") (pintype "passive"))
    )
    (net (code "117") (name "unconnected-(P4-Pad42)") (class "Default")
      (node (ref "P4") (pin "42") (pinfunction "42_42") (pintype "passive"))
    )
    (net (code "118") (name "unconnected-(P4-Pad43)") (class "Default")
      (node (ref "P4") (pin "43") (pinfunction "43_43") (pintype "passive"))
    )
    (net (code "119") (name "unconnected-(P4-Pad44)") (class "Default")
      (node (ref "P4") (pin "44") (pinfunction "44_44") (pintype "passive"))
    )
    (net (code "120") (name "unconnected-(P4-Pad45)") (class "Default")
      (node (ref "P4") (pin "45") (pinfunction "45_45") (pintype "passive"))
    )
    (net (code "121") (name "unconnected-(P4-Pad46)") (class "Default")
      (node (ref "P4") (pin "46") (pinfunction "46_46") (pintype "passive"))
    )
    (net (code "122") (name "unconnected-(P4-Pad47)") (class "Default")
      (node (ref "P4") (pin "47") (pinfunction "47_47") (pintype "passive"))
    )
    (net (code "123") (name "unconnected-(P4-Pad48)") (class "Default")
      (node (ref "P4") (pin "48") (pinfunction "48_48") (pintype "passive"))
    )
    (net (code "124") (name "unconnected-(P5-Pad5)") (class "Default")
      (node (ref "P5") (pin "5") (pinfunction "5_5") (pintype "passive"))
    )
    (net (code "125") (name "unconnected-(P5-Pad6)") (class "Default")
      (node (ref "P5") (pin "6") (pinfunction "6_6") (pintype "passive"))
    )
    (net (code "126") (name "unconnected-(P5-Pad7)") (class "Default")
      (node (ref "P5") (pin "7") (pinfunction "7_7") (pintype "passive"))
    )
    (net (code "127") (name "unconnected-(P5-Pad8)") (class "Default")
      (node (ref "P5") (pin "8") (pinfunction "8_8") (pintype "passive"))
    )
    (net (code "128") (name "unconnected-(P5-Pad9)") (class "Default")
      (node (ref "P5") (pin "9") (pinfunction "9_9") (pintype "passive"))
    )
    (net (code "129") (name "unconnected-(P5-Pad10)") (class "Default")
      (node (ref "P5") (pin "10") (pinfunction "10_10") (pintype "passive"))
    )
    (net (code "130") (name "unconnected-(P5-Pad11)") (class "Default")
      (node (ref "P5") (pin "11") (pinfunction "11_11") (pintype "passive"))
    )
    (net (code "131") (name "unconnected-(P5-Pad12)") (class "Default")
      (node (ref "P5") (pin "12") (pinfunction "12_12") (pintype "passive"))
    )
    (net (code "132") (name "unconnected-(P5-Pad13)") (class "Default")
      (node (ref "P5") (pin "13") (pinfunction "13_13") (pintype "passive"))
    )
    (net (code "133") (name "unconnected-(P5-Pad15)") (class "Default")
      (node (ref "P5") (pin "15") (pinfunction "15_15") (pintype "passive"))
    )
    (net (code "134") (name "unconnected-(P5-Pad17)") (class "Default")
      (node (ref "P5") (pin "17") (pinfunction "17_17") (pintype "passive"))
    )
    (net (code "135") (name "unconnected-(P5-Pad19)") (class "Default")
      (node (ref "P5") (pin "19") (pinfunction "19_19") (pintype "passive"))
    )
    (net (code "136") (name "unconnected-(P5-Pad20)") (class "Default")
      (node (ref "P5") (pin "20") (pinfunction "20_20") (pintype "passive"))
    )
    (net (code "137") (name "unconnected-(P5-Pad21)") (class "Default")
      (node (ref "P5") (pin "21") (pinfunction "21_21") (pintype "passive"))
    )
    (net (code "138") (name "unconnected-(P5-Pad22)") (class "Default")
      (node (ref "P5") (pin "22") (pinfunction "22_22") (pintype "passive"))
    )
    (net (code "139") (name "unconnected-(P5-Pad23)") (class "Default")
      (node (ref "P5") (pin "23") (pinfunction "23_23") (pintype "passive"))
    )
    (net (code "140") (name "unconnected-(P5-Pad24)") (class "Default")
      (node (ref "P5") (pin "24") (pinfunction "24_24") (pintype "passive"))
    )
    (net (code "141") (name "unconnected-(P5-Pad25)") (class "Default")
      (node (ref "P5") (pin "25") (pinfunction "25_25") (pintype "passive"))
    )
    (net (code "142") (name "unconnected-(P5-Pad26)") (class "Default")
      (node (ref "P5") (pin "26") (pinfunction "26_26") (pintype "passive"))
    )
    (net (code "143") (name "unconnected-(P5-Pad27)") (class "Default")
      (node (ref "P5") (pin "27") (pinfunction "27_27") (pintype "passive"))
    )
    (net (code "144") (name "unconnected-(P5-Pad28)") (class "Default")
      (node (ref "P5") (pin "28") (pinfunction "28_28") (pintype "passive"))
    )
    (net (code "145") (name "unconnected-(P5-Pad29)") (class "Default")
      (node (ref "P5") (pin "29") (pinfunction "29_29") (pintype "passive"))
    )
    (net (code "146") (name "unconnected-(P5-Pad30)") (class "Default")
      (node (ref "P5") (pin "30") (pinfunction "30_30") (pintype "passive"))
    )
    (net (code "147") (name "unconnected-(P5-Pad31)") (class "Default")
      (node (ref "P5") (pin "31") (pinfunction "31_31") (pintype "passive"))
    )
    (net (code "148") (name "unconnected-(P5-Pad32)") (class "Default")
      (node (ref "P5") (pin "32") (pinfunction "32_32") (pintype "passive"))
    )
    (net (code "149") (name "unconnected-(P5-Pad33)") (class "Default")
      (node (ref "P5") (pin "33") (pinfunction "33_33") (pintype "passive"))
    )
    (net (code "150") (name "unconnected-(P5-Pad34)") (class "Default")
      (node (ref "P5") (pin "34") (pinfunction "34_34") (pintype "passive"))
    )
    (net (code "151") (name "unconnected-(P5-Pad35)") (class "Default")
      (node (ref "P5") (pin "35") (pinfunction "35_35") (pintype "passive"))
    )
    (net (code "152") (name "unconnected-(P5-Pad36)") (class "Default")
      (node (ref "P5") (pin "36") (pinfunction "36_36") (pintype "passive"))
    )
    (net (code "153") (name "unconnected-(P5-Pad37)") (class "Default")
      (node (ref "P5") (pin "37") (pinfunction "37_37") (pintype "passive"))
    )
    (net (code "154") (name "unconnected-(P5-Pad38)") (class "Default")
      (node (ref "P5") (pin "38") (pinfunction "38_38") (pintype "passive"))
    )
    (net (code "155") (name "unconnected-(P5-Pad40)") (class "Default")
      (node (ref "P5") (pin "40") (pinfunction "40_40") (pintype "passive"))
    )
    (net (code "156") (name "unconnected-(P5-Pad41)") (class "Default")
      (node (ref "P5") (pin "41") (pinfunction "41_41") (pintype "passive"))
    )
    (net (code "157") (name "unconnected-(P5-Pad42)") (class "Default")
      (node (ref "P5") (pin "42") (pinfunction "42_42") (pintype "passive"))
    )
    (net (code "158") (name "unconnected-(P5-Pad44)") (class "Default")
      (node (ref "P5") (pin "44") (pinfunction "44_44") (pintype "passive"))
    )
    (net (code "159") (name "unconnected-(P5-Pad45)") (class "Default")
      (node (ref "P5") (pin "45") (pinfunction "45_45") (pintype "passive"))
    )
    (net (code "160") (name "unconnected-(P5-Pad46)") (class "Default")
      (node (ref "P5") (pin "46") (pinfunction "46_46") (pintype "passive"))
    )
    (net (code "161") (name "unconnected-(P5-Pad47)") (class "Default")
      (node (ref "P5") (pin "47") (pinfunction "47_47") (pintype "passive"))
    )
    (net (code "162") (name "unconnected-(P5-Pad48)") (class "Default")
      (node (ref "P5") (pin "48") (pinfunction "48_48") (pintype "passive"))
    )
    (net (code "163") (name "unconnected-(Q3-C-Pad3)") (class "Default")
      (node (ref "Q3") (pin "3") (pinfunction "C_3") (pintype "passive"))
    )
  )
)
